# LED_board_schematic_pg_1.net
KiCad netlist of a schematic drawn in Altium Designer
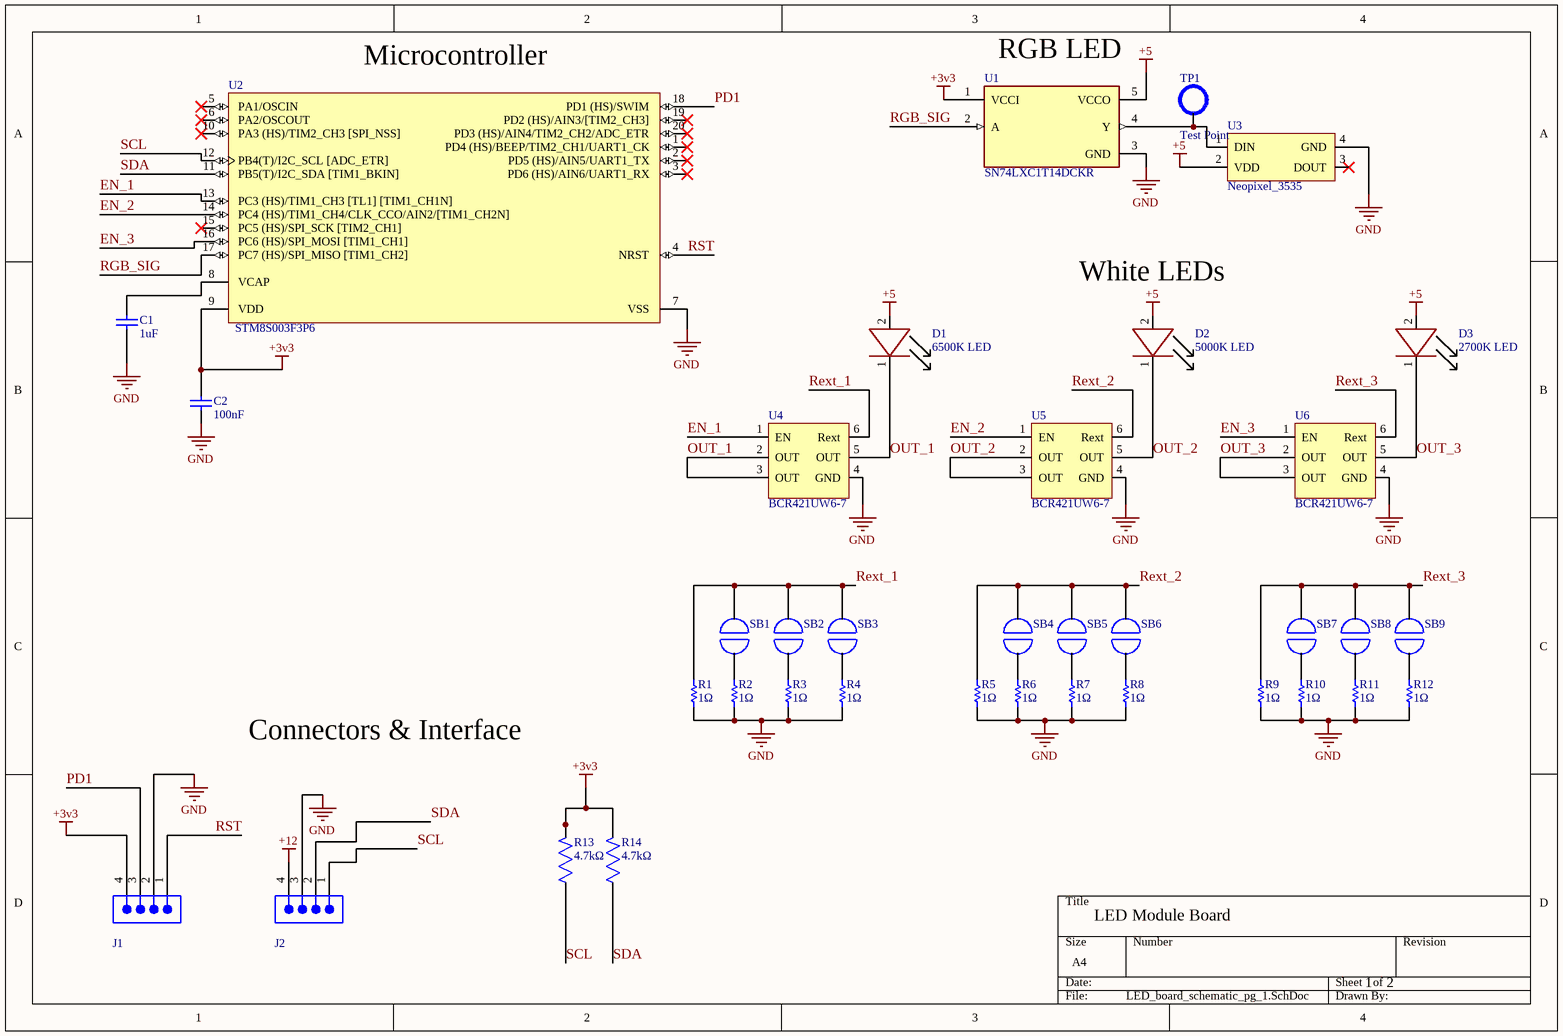
[diagram p0: LED_board_schematic_pg_1.SchDoc]

(export (version "E")
  (design (tool "Eeschema 10.0.6"))
  (components
    (comp (ref "C1")
      (value "1uF")
      (footprint "0402 PACKAGE")
      (description "CAP CER 1UF 10V X5R 0402")
      (libsource (lib "LED_Validation_Sch_Lib") (part "Capacitor"))
    )
    (comp (ref "C2")
      (value "100nF")
      (footprint "0402 PACKAGE")
      (description "CAP CER 0.1UF 10V X5R 0402")
      (libsource (lib "LED_Validation_Sch_Lib") (part "Capacitor"))
    )
    (comp (ref "D1")
      (value "6500K LED")
      (footprint "LED Package Top")
      (description "6500k LED")
      (libsource (lib "LED_board") (part "6500K LED"))
    )
    (comp (ref "D2")
      (value "5000K LED")
      (footprint "LED Package Top")
      (description "5000k LED")
      (libsource (lib "LED_board") (part "5000K LED"))
    )
    (comp (ref "D3")
      (value "2700K LED")
      (footprint "LED Package Top")
      (description "2700k LED")
      (libsource (lib "LED_board") (part "2700K LED"))
    )
    (comp (ref "J1")
      (value "61300411121")
      (footprint "61300411121")
      (libsource (lib "Altium Content Vault") (part "Header_Male_1R_04P"))
    )
    (comp (ref "J2")
      (value "61300411121")
      (footprint "61300411121")
      (libsource (lib "Altium Content Vault") (part "Header_Male_1R_04P"))
    )
    (comp (ref "R1")
      (value "1Ω")
      (footprint "RESC1609X50X30NL10T20")
      (fields (field (name "MANUFACTURER") "Vishay Dale") (field (name "PART NUMBER") "CRCW06031R00FKEA"))
      (libsource (lib "Altium Content Vault") (part "RES"))
    )
    (comp (ref "R2")
      (value "1Ω")
      (footprint "RESC1609X50X30NL10T20")
      (fields (field (name "MANUFACTURER") "Vishay Dale") (field (name "PART NUMBER") "CRCW06031R00FKEA"))
      (libsource (lib "Altium Content Vault") (part "RES"))
    )
    (comp (ref "R3")
      (value "1Ω")
      (footprint "RESC1609X50X30NL10T20")
      (fields (field (name "MANUFACTURER") "Vishay Dale") (field (name "PART NUMBER") "CRCW06031R00FKEA"))
      (libsource (lib "Altium Content Vault") (part "RES"))
    )
    (comp (ref "R4")
      (value "1Ω")
      (footprint "RESC1609X50X30NL10T20")
      (fields (field (name "MANUFACTURER") "Vishay Dale") (field (name "PART NUMBER") "CRCW06031R00FKEA"))
      (libsource (lib "Altium Content Vault") (part "RES"))
    )
    (comp (ref "R5")
      (value "1Ω")
      (footprint "RESC1609X50X30NL10T20")
      (fields (field (name "MANUFACTURER") "Vishay Dale") (field (name "PART NUMBER") "CRCW06031R00FKEA"))
      (libsource (lib "Altium Content Vault") (part "RES"))
    )
    (comp (ref "R6")
      (value "1Ω")
      (footprint "RESC1609X50X30NL10T20")
      (fields (field (name "MANUFACTURER") "Vishay Dale") (field (name "PART NUMBER") "CRCW06031R00FKEA"))
      (libsource (lib "Altium Content Vault") (part "RES"))
    )
    (comp (ref "R7")
      (value "1Ω")
      (footprint "RESC1609X50X30NL10T20")
      (fields (field (name "MANUFACTURER") "Vishay Dale") (field (name "PART NUMBER") "CRCW06031R00FKEA"))
      (libsource (lib "Altium Content Vault") (part "RES"))
    )
    (comp (ref "R8")
      (value "1Ω")
      (footprint "RESC1609X50X30NL10T20")
      (fields (field (name "MANUFACTURER") "Vishay Dale") (field (name "PART NUMBER") "CRCW06031R00FKEA"))
      (libsource (lib "Altium Content Vault") (part "RES"))
    )
    (comp (ref "R9")
      (value "1Ω")
      (footprint "RESC1609X50X30NL10T20")
      (fields (field (name "MANUFACTURER") "Vishay Dale") (field (name "PART NUMBER") "CRCW06031R00FKEA"))
      (libsource (lib "Altium Content Vault") (part "RES"))
    )
    (comp (ref "R10")
      (value "1Ω")
      (footprint "RESC1609X50X30NL10T20")
      (fields (field (name "MANUFACTURER") "Vishay Dale") (field (name "PART NUMBER") "CRCW06031R00FKEA"))
      (libsource (lib "Altium Content Vault") (part "RES"))
    )
    (comp (ref "R11")
      (value "1Ω")
      (footprint "RESC1609X50X30NL10T20")
      (fields (field (name "MANUFACTURER") "Vishay Dale") (field (name "PART NUMBER") "CRCW06031R00FKEA"))
      (libsource (lib "Altium Content Vault") (part "RES"))
    )
    (comp (ref "R12")
      (value "1Ω")
      (footprint "RESC1609X50X30NL10T20")
      (fields (field (name "MANUFACTURER") "Vishay Dale") (field (name "PART NUMBER") "CRCW06031R00FKEA"))
      (libsource (lib "Altium Content Vault") (part "RES"))
    )
    (comp (ref "R13")
      (value "4.7kΩ")
      (footprint "0402 PACKAGE")
      (libsource (lib "LED_Validation_Sch_Lib") (part "Resistor"))
    )
    (comp (ref "R14")
      (value "4.7kΩ")
      (footprint "0402 PACKAGE")
      (libsource (lib "LED_Validation_Sch_Lib") (part "Resistor"))
    )
    (comp (ref "SB1")
      (value "Solder Bridge")
      (footprint "Solder Bridge")
      (libsource (lib "LED_board") (part "Solder Bridge"))
    )
    (comp (ref "SB2")
      (value "Solder Bridge")
      (footprint "Solder Bridge")
      (libsource (lib "LED_board") (part "Solder Bridge"))
    )
    (comp (ref "SB3")
      (value "Solder Bridge")
      (footprint "Solder Bridge")
      (libsource (lib "LED_board") (part "Solder Bridge"))
    )
    (comp (ref "SB4")
      (value "Solder Bridge")
      (footprint "Solder Bridge")
      (libsource (lib "LED_board") (part "Solder Bridge"))
    )
    (comp (ref "SB5")
      (value "Solder Bridge")
      (footprint "Solder Bridge")
      (libsource (lib "LED_board") (part "Solder Bridge"))
    )
    (comp (ref "SB6")
      (value "Solder Bridge")
      (footprint "Solder Bridge")
      (libsource (lib "LED_board") (part "Solder Bridge"))
    )
    (comp (ref "SB7")
      (value "Solder Bridge")
      (footprint "Solder Bridge")
      (libsource (lib "LED_board") (part "Solder Bridge"))
    )
    (comp (ref "SB8")
      (value "Solder Bridge")
      (footprint "Solder Bridge")
      (libsource (lib "LED_board") (part "Solder Bridge"))
    )
    (comp (ref "SB9")
      (value "Solder Bridge")
      (footprint "Solder Bridge")
      (libsource (lib "LED_board") (part "Solder Bridge"))
    )
    (comp (ref "TP1")
      (value "Test Point")
      (footprint "Test Point")
      (libsource (lib "LED_board") (part "Test Point"))
    )
    (comp (ref "U1")
      (value "SN74LXC1T14DCKR")
      (footprint "FP-DCK0005A-MFG")
      (description "IC TRANSLATOR UNIDIR SC70-5")
      (libsource (lib "Altium Content Vault") (part "307c293e8a03021d4f984951ede828e"))
    )
    (comp (ref "U2")
      (value "STM8S003F3P6")
      (footprint "STM-TSSOP20_V")
      (fields (field (name "MANUFACTURER") "STMicroelectronics"))
      (libsource (lib "Altium Content Vault") (part "STM-STM8S003F3P6-TSSOP20"))
    )
    (comp (ref "U3")
      (value "Neopixel_3535")
      (footprint "Neopixel")
      (libsource (lib "LED_Validation_Sch_Lib") (part "Neopixel_3535"))
    )
    (comp (ref "U4")
      (value "BCR421UW6-7")
      (footprint "SOT95P280X140-6N")
      (description "LED Driver")
      (libsource (lib "LED_Validation_Sch_Lib") (part "BCR421UW6-7"))
    )
    (comp (ref "U5")
      (value "BCR421UW6-7")
      (footprint "SOT95P280X140-6N")
      (description "LED Driver")
      (libsource (lib "LED_Validation_Sch_Lib") (part "BCR421UW6-7"))
    )
    (comp (ref "U6")
      (value "BCR421UW6-7")
      (footprint "SOT95P280X140-6N")
      (description "LED Driver")
      (libsource (lib "LED_Validation_Sch_Lib") (part "BCR421UW6-7"))
    )
  )
  (nets
    (net (code "1") (name "+3v3") (class "Default")
      (node (ref "C2") (pin "2") (pinfunction "2_2") (pintype "passive"))
      (node (ref "J1") (pin "4") (pinfunction "4_4") (pintype "passive"))
      (node (ref "R13") (pin "2") (pinfunction "2_2") (pintype "passive"))
      (node (ref "R14") (pin "2") (pinfunction "2_2") (pintype "passive"))
      (node (ref "U1") (pin "1") (pinfunction "VCCI_1") (pintype "power_in"))
      (node (ref "U2") (pin "9") (pinfunction "VDD_9") (pintype "power_in"))
    )
    (net (code "2") (name "+5") (class "Default")
      (node (ref "D1") (pin "2") (pinfunction "2_2") (pintype "passive"))
      (node (ref "D2") (pin "2") (pinfunction "2_2") (pintype "passive"))
      (node (ref "D3") (pin "2") (pinfunction "2_2") (pintype "passive"))
      (node (ref "U1") (pin "5") (pinfunction "VCCO_5") (pintype "power_in"))
      (node (ref "U3") (pin "2") (pinfunction "VDD_2") (pintype "passive"))
    )
    (net (code "3") (name "+12") (class "Default")
      (node (ref "J2") (pin "4") (pinfunction "4_4") (pintype "passive"))
    )
    (net (code "4") (name "/EN_1") (class "Default")
      (node (ref "U2") (pin "13") (pinfunction "PC3_(HS)/TIM1_CH3_[TL1]_[TIM1_CH1N]_13") (pintype "bidirectional"))
      (node (ref "U4") (pin "1") (pinfunction "EN_1") (pintype "passive"))
    )
    (net (code "5") (name "/EN_2") (class "Default")
      (node (ref "U2") (pin "14") (pinfunction "PC4_(HS)/TIM1_CH4/CLK_CCO/AIN2/[TIM1_CH2N]_14") (pintype "bidirectional"))
      (node (ref "U5") (pin "1") (pinfunction "EN_1") (pintype "passive"))
    )
    (net (code "6") (name "/EN_3") (class "Default")
      (node (ref "U2") (pin "16") (pinfunction "PC6_(HS)/SPI_MOSI_[TIM1_CH1]_16") (pintype "bidirectional"))
      (node (ref "U6") (pin "1") (pinfunction "EN_1") (pintype "passive"))
    )
    (net (code "7") (name "/OUT_1") (class "Default")
      (node (ref "D1") (pin "1") (pinfunction "1_1") (pintype "passive"))
      (node (ref "U4") (pin "2") (pinfunction "OUT_2") (pintype "passive"))
      (node (ref "U4") (pin "3") (pinfunction "OUT_3") (pintype "passive"))
      (node (ref "U4") (pin "5") (pinfunction "OUT_5") (pintype "passive"))
    )
    (net (code "8") (name "/OUT_2") (class "Default")
      (node (ref "D2") (pin "1") (pinfunction "1_1") (pintype "passive"))
      (node (ref "U5") (pin "2") (pinfunction "OUT_2") (pintype "passive"))
      (node (ref "U5") (pin "3") (pinfunction "OUT_3") (pintype "passive"))
      (node (ref "U5") (pin "5") (pinfunction "OUT_5") (pintype "passive"))
    )
    (net (code "9") (name "/OUT_3") (class "Default")
      (node (ref "D3") (pin "1") (pinfunction "1_1") (pintype "passive"))
      (node (ref "U6") (pin "2") (pinfunction "OUT_2") (pintype "passive"))
      (node (ref "U6") (pin "3") (pinfunction "OUT_3") (pintype "passive"))
      (node (ref "U6") (pin "5") (pinfunction "OUT_5") (pintype "passive"))
    )
    (net (code "10") (name "/PD1") (class "Default")
      (node (ref "J1") (pin "3") (pinfunction "3_3") (pintype "passive"))
      (node (ref "U2") (pin "18") (pinfunction "PD1_(HS)/SWIM_18") (pintype "bidirectional"))
    )
    (net (code "11") (name "/RGB_SIG") (class "Default")
      (node (ref "U1") (pin "2") (pinfunction "A_2") (pintype "input"))
      (node (ref "U2") (pin "17") (pinfunction "PC7_(HS)/SPI_MISO_[TIM1_CH2]_17") (pintype "bidirectional"))
    )
    (net (code "12") (name "/RST") (class "Default")
      (node (ref "J1") (pin "1") (pinfunction "1_1") (pintype "passive"))
      (node (ref "U2") (pin "4") (pinfunction "NRST_4") (pintype "bidirectional"))
    )
    (net (code "13") (name "/Rext_1") (class "Default")
      (node (ref "R1") (pin "2") (pinfunction "2_2") (pintype "passive"))
      (node (ref "SB1") (pin "1") (pinfunction "1_1") (pintype "passive"))
      (node (ref "SB2") (pin "1") (pinfunction "1_1") (pintype "passive"))
      (node (ref "SB3") (pin "1") (pinfunction "1_1") (pintype "passive"))
      (node (ref "U4") (pin "6") (pinfunction "Rext_6") (pintype "passive"))
    )
    (net (code "14") (name "/Rext_2") (class "Default")
      (node (ref "R5") (pin "2") (pinfunction "2_2") (pintype "passive"))
      (node (ref "SB4") (pin "1") (pinfunction "1_1") (pintype "passive"))
      (node (ref "SB5") (pin "1") (pinfunction "1_1") (pintype "passive"))
      (node (ref "SB6") (pin "1") (pinfunction "1_1") (pintype "passive"))
      (node (ref "U5") (pin "6") (pinfunction "Rext_6") (pintype "passive"))
    )
    (net (code "15") (name "/Rext_3") (class "Default")
      (node (ref "R9") (pin "2") (pinfunction "2_2") (pintype "passive"))
      (node (ref "SB7") (pin "1") (pinfunction "1_1") (pintype "passive"))
      (node (ref "SB8") (pin "1") (pinfunction "1_1") (pintype "passive"))
      (node (ref "SB9") (pin "1") (pinfunction "1_1") (pintype "passive"))
      (node (ref "U6") (pin "6") (pinfunction "Rext_6") (pintype "passive"))
    )
    (net (code "16") (name "/SCL") (class "Default")
      (node (ref "J2") (pin "1") (pinfunction "1_1") (pintype "passive"))
      (node (ref "R13") (pin "1") (pinfunction "1_1") (pintype "passive"))
      (node (ref "U2") (pin "12") (pinfunction "PB4(T)/I2C_SCL_[ADC_ETR]_12") (pintype "bidirectional"))
    )
    (net (code "17") (name "/SDA") (class "Default")
      (node (ref "J2") (pin "2") (pinfunction "2_2") (pintype "passive"))
      (node (ref "R14") (pin "1") (pinfunction "1_1") (pintype "passive"))
      (node (ref "U2") (pin "11") (pinfunction "PB5(T)/I2C_SDA_[TIM1_BKIN]_11") (pintype "bidirectional"))
    )
    (net (code "18") (name "GND") (class "Default")
      (node (ref "C1") (pin "1") (pinfunction "1_1") (pintype "passive"))
      (node (ref "C2") (pin "1") (pinfunction "1_1") (pintype "passive"))
      (node (ref "J1") (pin "2") (pinfunction "2_2") (pintype "passive"))
      (node (ref "J2") (pin "3") (pinfunction "3_3") (pintype "passive"))
      (node (ref "R1") (pin "1") (pinfunction "1_1") (pintype "passive"))
      (node (ref "R10") (pin "1") (pinfunction "1_1") (pintype "passive"))
      (node (ref "R11") (pin "1") (pinfunction "1_1") (pintype "passive"))
      (node (ref "R12") (pin "1") (pinfunction "1_1") (pintype "passive"))
      (node (ref "R2") (pin "1") (pinfunction "1_1") (pintype "passive"))
      (node (ref "R3") (pin "1") (pinfunction "1_1") (pintype "passive"))
      (node (ref "R4") (pin "1") (pinfunction "1_1") (pintype "passive"))
      (node (ref "R5") (pin "1") (pinfunction "1_1") (pintype "passive"))
      (node (ref "R6") (pin "1") (pinfunction "1_1") (pintype "passive"))
      (node (ref "R7") (pin "1") (pinfunction "1_1") (pintype "passive"))
      (node (ref "R8") (pin "1") (pinfunction "1_1") (pintype "passive"))
      (node (ref "R9") (pin "1") (pinfunction "1_1") (pintype "passive"))
      (node (ref "U1") (pin "3") (pinfunction "GND_3") (pintype "power_in"))
      (node (ref "U2") (pin "7") (pinfunction "VSS_7") (pintype "power_in"))
      (node (ref "U3") (pin "4") (pinfunction "GND_4") (pintype "passive"))
      (node (ref "U4") (pin "4") (pinfunction "GND_4") (pintype "passive"))
      (node (ref "U5") (pin "4") (pinfunction "GND_4") (pintype "passive"))
      (node (ref "U6") (pin "4") (pinfunction "GND_4") (pintype "passive"))
    )
    (net (code "19") (name "Net-(R2-Pad2)") (class "Default")
      (node (ref "R2") (pin "2") (pinfunction "2_2") (pintype "passive"))
      (node (ref "SB1") (pin "2") (pinfunction "2_2") (pintype "passive"))
    )
    (net (code "20") (name "Net-(R3-Pad2)") (class "Default")
      (node (ref "R3") (pin "2") (pinfunction "2_2") (pintype "passive"))
      (node (ref "SB2") (pin "2") (pinfunction "2_2") (pintype "passive"))
    )
    (net (code "21") (name "Net-(R4-Pad2)") (class "Default")
      (node (ref "R4") (pin "2") (pinfunction "2_2") (pintype "passive"))
      (node (ref "SB3") (pin "2") (pinfunction "2_2") (pintype "passive"))
    )
    (net (code "22") (name "Net-(R6-Pad2)") (class "Default")
      (node (ref "R6") (pin "2") (pinfunction "2_2") (pintype "passive"))
      (node (ref "SB4") (pin "2") (pinfunction "2_2") (pintype "passive"))
    )
    (net (code "23") (name "Net-(R7-Pad2)") (class "Default")
      (node (ref "R7") (pin "2") (pinfunction "2_2") (pintype "passive"))
      (node (ref "SB5") (pin "2") (pinfunction "2_2") (pintype "passive"))
    )
    (net (code "24") (name "Net-(R8-Pad2)") (class "Default")
      (node (ref "R8") (pin "2") (pinfunction "2_2") (pintype "passive"))
      (node (ref "SB6") (pin "2") (pinfunction "2_2") (pintype "passive"))
    )
    (net (code "25") (name "Net-(R10-Pad2)") (class "Default")
      (node (ref "R10") (pin "2") (pinfunction "2_2") (pintype "passive"))
      (node (ref "SB7") (pin "2") (pinfunction "2_2") (pintype "passive"))
    )
    (net (code "26") (name "Net-(R11-Pad2)") (class "Default")
      (node (ref "R11") (pin "2") (pinfunction "2_2") (pintype "passive"))
      (node (ref "SB8") (pin "2") (pinfunction "2_2") (pintype "passive"))
    )
    (net (code "27") (name "Net-(R12-Pad2)") (class "Default")
      (node (ref "R12") (pin "2") (pinfunction "2_2") (pintype "passive"))
      (node (ref "SB9") (pin "2") (pinfunction "2_2") (pintype "passive"))
    )
    (net (code "28") (name "Net-(U1-Y)") (class "Default")
      (node (ref "TP1") (pin "1") (pinfunction "1_1") (pintype "passive"))
      (node (ref "U1") (pin "4") (pinfunction "Y_4") (pintype "output"))
      (node (ref "U3") (pin "1") (pinfunction "DIN_1") (pintype "passive"))
    )
    (net (code "29") (name "Net-(U2-VCAP)") (class "Default")
      (node (ref "C1") (pin "2") (pinfunction "2_2") (pintype "passive"))
      (node (ref "U2") (pin "8") (pinfunction "VCAP_8") (pintype "power_in"))
    )
    (net (code "30") (name "unconnected-(U2-PA1{slash}OSCIN-Pad5)") (class "Default")
      (node (ref "U2") (pin "5") (pinfunction "PA1/OSCIN_5") (pintype "bidirectional+no_connect"))
    )
    (net (code "31") (name "unconnected-(U2-PA2{slash}OSCOUT-Pad6)") (class "Default")
      (node (ref "U2") (pin "6") (pinfunction "PA2/OSCOUT_6") (pintype "bidirectional+no_connect"))
    )
    (net (code "32") (name "unconnected-(U2-PA3_(HS){slash}TIM2_CH3_[SPI_NSS]-Pad10)") (class "Default")
      (node (ref "U2") (pin "10") (pinfunction "PA3_(HS)/TIM2_CH3_[SPI_NSS]_10") (pintype "bidirectional+no_connect"))
    )
    (net (code "33") (name "unconnected-(U2-PC5_(HS){slash}SPI_SCK_[TIM2_CH1]-Pad15)") (class "Default")
      (node (ref "U2") (pin "15") (pinfunction "PC5_(HS)/SPI_SCK_[TIM2_CH1]_15") (pintype "bidirectional+no_connect"))
    )
    (net (code "34") (name "unconnected-(U2-PD2_(HS){slash}AIN3{slash}[TIM2_CH3]-Pad19)") (class "Default")
      (node (ref "U2") (pin "19") (pinfunction "PD2_(HS)/AIN3/[TIM2_CH3]_19") (pintype "bidirectional+no_connect"))
    )
    (net (code "35") (name "unconnected-(U2-PD3_(HS){slash}AIN4{slash}TIM2_CH2{slash}ADC_ETR-Pad20)") (class "Default")
      (node (ref "U2") (pin "20") (pinfunction "PD3_(HS)/AIN4/TIM2_CH2/ADC_ETR_20") (pintype "bidirectional+no_connect"))
    )
    (net (code "36") (name "unconnected-(U2-PD4_(HS){slash}BEEP{slash}TIM2_CH1{slash}UART1_CK-Pad1)") (class "Default")
      (node (ref "U2") (pin "1") (pinfunction "PD4_(HS)/BEEP/TIM2_CH1/UART1_CK_1") (pintype "bidirectional+no_connect"))
    )
    (net (code "37") (name "unconnected-(U2-PD5_(HS){slash}AIN5{slash}UART1_TX-Pad2)") (class "Default")
      (node (ref "U2") (pin "2") (pinfunction "PD5_(HS)/AIN5/UART1_TX_2") (pintype "bidirectional+no_connect"))
    )
    (net (code "38") (name "unconnected-(U2-PD6_(HS){slash}AIN6{slash}UART1_RX-Pad3)") (class "Default")
      (node (ref "U2") (pin "3") (pinfunction "PD6_(HS)/AIN6/UART1_RX_3") (pintype "bidirectional+no_connect"))
    )
    (net (code "39") (name "unconnected-(U3-DOUT-Pad3)") (class "Default")
      (node (ref "U3") (pin "3") (pinfunction "DOUT_3") (pintype "passive+no_connect"))
    )
  )
)
